# power_block.net
KiCad netlist of a schematic drawn in Altium Designer
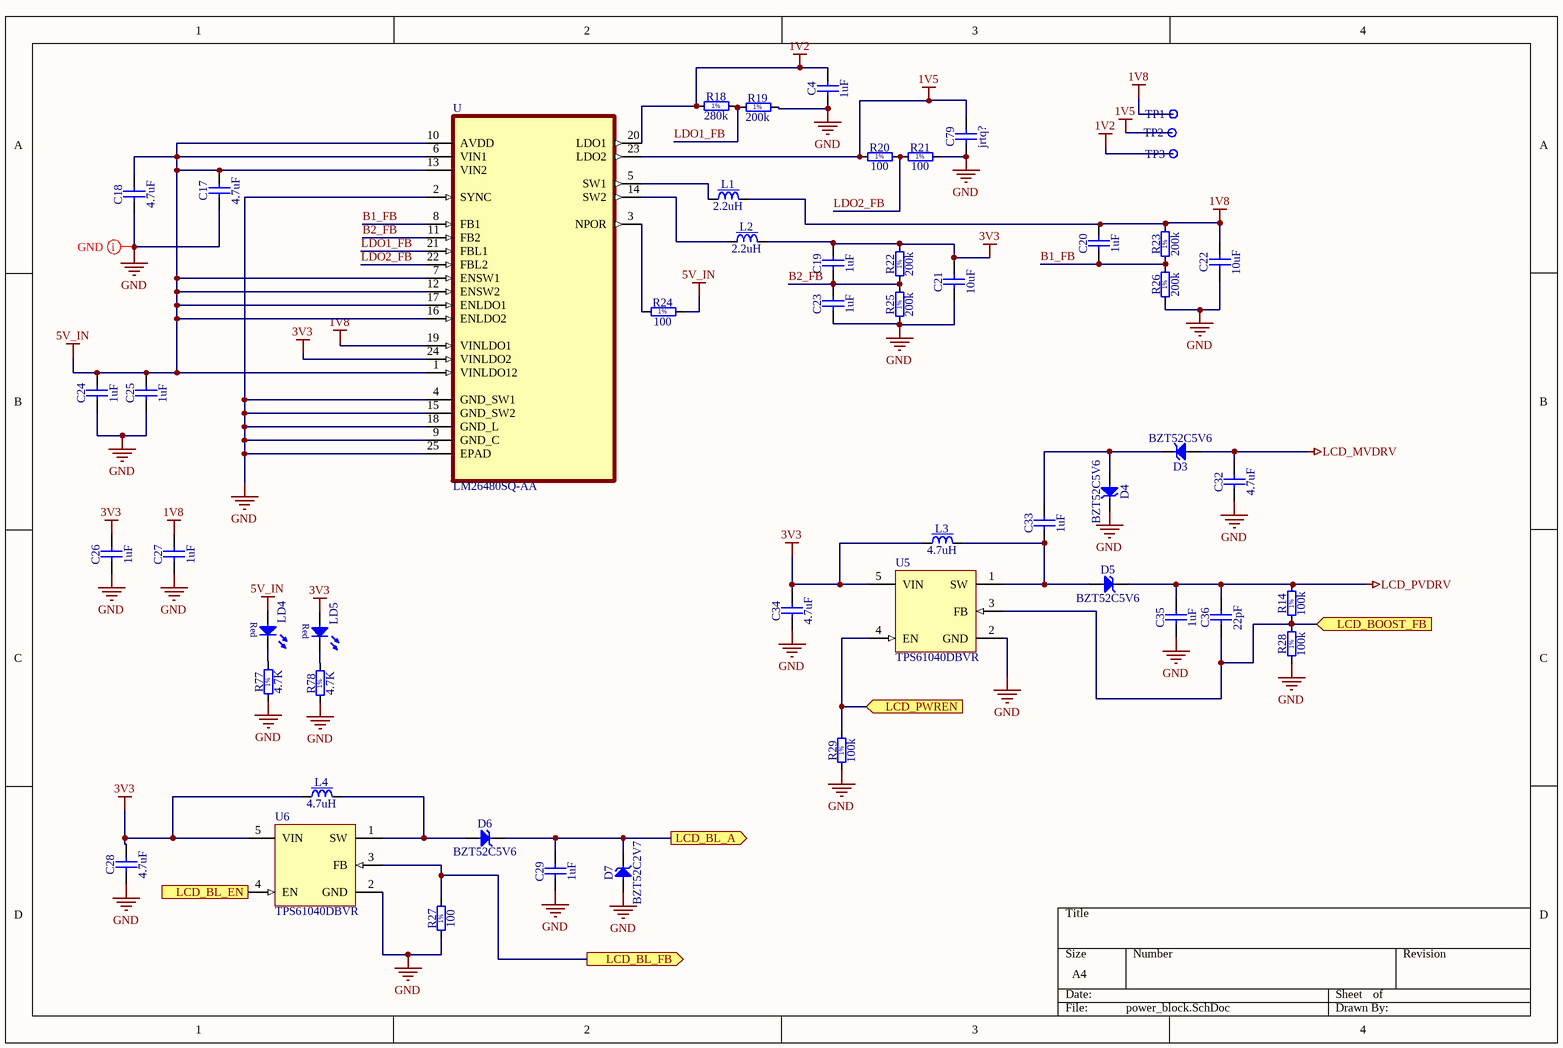
[diagram p0: power_block.SchDoc]

(export (version "E")
  (design (tool "Eeschema 10.0.6"))
  (components
    (comp (ref "C4")
      (value "1uF")
      (footprint "CAPC2013X100N")
      (description "Non-polarised capacitor")
      (fields
        (field (name "PART NUMBER") "CC0805_1.5NF_50V_5%_C0G")
        (field (name "VOLTAGE") "50V")
        (field (name "AUTHOR") "CERN DEM BC")
      )
      (libsource (lib "Capacitors") (part "Capacitor - non polarized"))
    )
    (comp (ref "C17")
      (value "4.7uF")
      (footprint "CAPC2013X100N")
      (description "Non-polarised capacitor")
      (fields
        (field (name "PART NUMBER") "CC0805_1.5NF_50V_5%_C0G")
        (field (name "VOLTAGE") "50V")
        (field (name "AUTHOR") "CERN DEM BC")
      )
      (libsource (lib "Capacitors") (part "Capacitor - non polarized"))
    )
    (comp (ref "C18")
      (value "4.7uF")
      (footprint "CAPC2013X100N")
      (description "Non-polarised capacitor")
      (fields
        (field (name "PART NUMBER") "CC0805_1.5NF_50V_5%_C0G")
        (field (name "VOLTAGE") "50V")
        (field (name "AUTHOR") "CERN DEM BC")
      )
      (libsource (lib "Capacitors") (part "Capacitor - non polarized"))
    )
    (comp (ref "C19")
      (value "1uF")
      (footprint "CAPC2013X100N")
      (description "Non-polarised capacitor")
      (fields
        (field (name "PART NUMBER") "CC0805_1.5NF_50V_5%_C0G")
        (field (name "VOLTAGE") "50V")
        (field (name "AUTHOR") "CERN DEM BC")
      )
      (libsource (lib "Capacitors") (part "Capacitor - non polarized"))
    )
    (comp (ref "C20")
      (value "1uF")
      (footprint "CAPC2013X100N")
      (description "Non-polarised capacitor")
      (fields
        (field (name "PART NUMBER") "CC0805_1.5NF_50V_5%_C0G")
        (field (name "VOLTAGE") "50V")
        (field (name "AUTHOR") "CERN DEM BC")
      )
      (libsource (lib "Capacitors") (part "Capacitor - non polarized"))
    )
    (comp (ref "C21")
      (value "10uF")
      (footprint "CAPC2013X100N")
      (description "Non-polarised capacitor")
      (fields
        (field (name "PART NUMBER") "CC0805_1.5NF_50V_5%_C0G")
        (field (name "VOLTAGE") "50V")
        (field (name "AUTHOR") "CERN DEM BC")
      )
      (libsource (lib "Capacitors") (part "Capacitor - non polarized"))
    )
    (comp (ref "C22")
      (value "10uF")
      (footprint "CAPC2013X100N")
      (description "Non-polarised capacitor")
      (fields
        (field (name "PART NUMBER") "CC0805_1.5NF_50V_5%_C0G")
        (field (name "VOLTAGE") "50V")
        (field (name "AUTHOR") "CERN DEM BC")
      )
      (libsource (lib "Capacitors") (part "Capacitor - non polarized"))
    )
    (comp (ref "C23")
      (value "1uF")
      (footprint "CAPC2013X100N")
      (description "Non-polarised capacitor")
      (fields
        (field (name "PART NUMBER") "CC0805_1.5NF_50V_5%_C0G")
        (field (name "VOLTAGE") "50V")
        (field (name "AUTHOR") "CERN DEM BC")
      )
      (libsource (lib "Capacitors") (part "Capacitor - non polarized"))
    )
    (comp (ref "C24")
      (value "1uF")
      (footprint "CAPC2013X100N")
      (description "Non-polarised capacitor")
      (fields
        (field (name "PART NUMBER") "CC0805_1.5NF_50V_5%_C0G")
        (field (name "VOLTAGE") "50V")
        (field (name "AUTHOR") "CERN DEM BC")
      )
      (libsource (lib "Capacitors") (part "Capacitor - non polarized"))
    )
    (comp (ref "C25")
      (value "1uF")
      (footprint "CAPC2013X100N")
      (description "Non-polarised capacitor")
      (fields
        (field (name "PART NUMBER") "CC0805_1.5NF_50V_5%_C0G")
        (field (name "VOLTAGE") "50V")
        (field (name "AUTHOR") "CERN DEM BC")
      )
      (libsource (lib "Capacitors") (part "Capacitor - non polarized"))
    )
    (comp (ref "C26")
      (value "1uF")
      (footprint "CAPC2013X100N")
      (description "Non-polarised capacitor")
      (fields
        (field (name "PART NUMBER") "CC0805_1.5NF_50V_5%_C0G")
        (field (name "VOLTAGE") "50V")
        (field (name "AUTHOR") "CERN DEM BC")
      )
      (libsource (lib "Capacitors") (part "Capacitor - non polarized"))
    )
    (comp (ref "C27")
      (value "1uF")
      (footprint "CAPC2013X100N")
      (description "Non-polarised capacitor")
      (fields
        (field (name "PART NUMBER") "CC0805_1.5NF_50V_5%_C0G")
        (field (name "VOLTAGE") "50V")
        (field (name "AUTHOR") "CERN DEM BC")
      )
      (libsource (lib "Capacitors") (part "Capacitor - non polarized"))
    )
    (comp (ref "C28")
      (value "4.7uF")
      (footprint "CAPC2013X100N")
      (description "Non-polarised capacitor")
      (fields
        (field (name "PART NUMBER") "CC0805_1.5NF_50V_5%_C0G")
        (field (name "VOLTAGE") "50V")
        (field (name "AUTHOR") "CERN DEM BC")
      )
      (libsource (lib "Capacitors") (part "Capacitor - non polarized"))
    )
    (comp (ref "C29")
      (value "1uF")
      (footprint "CAPC2013X100N")
      (description "Non-polarised capacitor")
      (fields
        (field (name "PART NUMBER") "CC0805_1.5NF_50V_5%_C0G")
        (field (name "VOLTAGE") "50V")
        (field (name "AUTHOR") "CERN DEM BC")
      )
      (libsource (lib "Capacitors") (part "Capacitor - non polarized"))
    )
    (comp (ref "C32")
      (value "4.7uF")
      (footprint "CAPC2013X100N")
      (description "Non-polarised capacitor")
      (fields
        (field (name "PART NUMBER") "CC0805_1.5NF_50V_5%_C0G")
        (field (name "VOLTAGE") "50V")
        (field (name "AUTHOR") "CERN DEM BC")
      )
      (libsource (lib "Capacitors") (part "Capacitor - non polarized"))
    )
    (comp (ref "C33")
      (value "1uF")
      (footprint "CAPC2013X100N")
      (description "Non-polarised capacitor")
      (fields
        (field (name "PART NUMBER") "CC0805_1.5NF_50V_5%_C0G")
        (field (name "VOLTAGE") "50V")
        (field (name "AUTHOR") "CERN DEM BC")
      )
      (libsource (lib "Capacitors") (part "Capacitor - non polarized"))
    )
    (comp (ref "C34")
      (value "4.7uF")
      (footprint "CAPC2013X100N")
      (description "Non-polarised capacitor")
      (fields
        (field (name "PART NUMBER") "CC0805_1.5NF_50V_5%_C0G")
        (field (name "VOLTAGE") "50V")
        (field (name "AUTHOR") "CERN DEM BC")
      )
      (libsource (lib "Capacitors") (part "Capacitor - non polarized"))
    )
    (comp (ref "C35")
      (value "1uF")
      (footprint "CAPC2013X100N")
      (description "Non-polarised capacitor")
      (fields
        (field (name "PART NUMBER") "CC0805_1.5NF_50V_5%_C0G")
        (field (name "VOLTAGE") "50V")
        (field (name "AUTHOR") "CERN DEM BC")
      )
      (libsource (lib "Capacitors") (part "Capacitor - non polarized"))
    )
    (comp (ref "C36")
      (value "22pF")
      (footprint "CAPC2013X100N")
      (description "Non-polarised capacitor")
      (fields
        (field (name "PART NUMBER") "CC0805_1.5NF_50V_5%_C0G")
        (field (name "VOLTAGE") "50V")
        (field (name "AUTHOR") "CERN DEM BC")
      )
      (libsource (lib "Capacitors") (part "Capacitor - non polarized"))
    )
    (comp (ref "C79")
      (value "jrtq?")
      (footprint "CAPC2013X100N")
      (description "Non-polarised capacitor")
      (fields
        (field (name "PART NUMBER") "CC0805_1.5NF_50V_5%_C0G")
        (field (name "VOLTAGE") "50V")
        (field (name "AUTHOR") "CERN DEM BC")
      )
      (libsource (lib "Capacitors") (part "Capacitor - non polarized"))
    )
    (comp (ref "D3")
      (value "BZT52C5V6")
      (footprint "SOD3715X145N")
      (description "Zener Diode")
      (fields
        (field (name "VOLTAGE") "5V6")
        (field (name "POWER") "0.5W")
        (field (name "AUTHOR") "CERN DEM JLC")
      )
      (libsource (lib "ICs And Semiconductors") (part "Diode Zener"))
    )
    (comp (ref "D4")
      (value "BZT52C5V6")
      (footprint "SOD3715X145N")
      (description "Zener Diode")
      (fields
        (field (name "VOLTAGE") "5V6")
        (field (name "POWER") "0.5W")
        (field (name "AUTHOR") "CERN DEM JLC")
      )
      (libsource (lib "ICs And Semiconductors") (part "Diode Zener"))
    )
    (comp (ref "D5")
      (value "BZT52C5V6")
      (footprint "SOD3715X145N")
      (description "Zener Diode")
      (fields
        (field (name "VOLTAGE") "5V6")
        (field (name "POWER") "0.5W")
        (field (name "AUTHOR") "CERN DEM JLC")
      )
      (libsource (lib "ICs And Semiconductors") (part "Diode Zener"))
    )
    (comp (ref "D6")
      (value "BZT52C5V6")
      (footprint "SOD3715X145N")
      (description "Zener Diode")
      (fields
        (field (name "VOLTAGE") "5V6")
        (field (name "POWER") "0.5W")
        (field (name "AUTHOR") "CERN DEM JLC")
      )
      (libsource (lib "ICs And Semiconductors") (part "Diode Zener"))
    )
    (comp (ref "D7")
      (value "BZT52C2V7")
      (footprint "SOD3715X145N")
      (description "Zener Diode")
      (fields
        (field (name "VOLTAGE") "2V7")
        (field (name "POWER") "500mW")
        (field (name "AUTHOR") "CERN DEM JLC")
      )
      (libsource (lib "ICs And Semiconductors") (part "Diode Zener"))
    )
    (comp (ref "L1")
      (value "2.2uH")
      (footprint "IND_MURATA-PS_8200")
      (description "Inductor With Core")
      (fields
        (field (name "PART NUMBER") "IND_22UH_10%_MURATA-PS_8200")
        (field (name "POWER") "320mA")
        (field (name "AUTHOR") "CERN DEM JMW")
      )
      (libsource (lib "Inductors & Transformers") (part "Inductor With Magnetic core"))
    )
    (comp (ref "L2")
      (value "2.2uH")
      (footprint "IND_MURATA-PS_8200")
      (description "Inductor With Core")
      (fields
        (field (name "PART NUMBER") "IND_22UH_10%_MURATA-PS_8200")
        (field (name "POWER") "320mA")
        (field (name "AUTHOR") "CERN DEM JMW")
      )
      (libsource (lib "Inductors & Transformers") (part "Inductor With Magnetic core"))
    )
    (comp (ref "L3")
      (value "4.7uH")
      (footprint "IND_MURATA-PS_8200")
      (description "Inductor With Core")
      (fields
        (field (name "PART NUMBER") "IND_22UH_10%_MURATA-PS_8200")
        (field (name "POWER") "320mA")
        (field (name "AUTHOR") "CERN DEM JMW")
      )
      (libsource (lib "Inductors & Transformers") (part "Inductor With Magnetic core"))
    )
    (comp (ref "L4")
      (value "4.7uH")
      (footprint "IND_MURATA-PS_8200")
      (description "Inductor With Core")
      (fields
        (field (name "PART NUMBER") "IND_22UH_10%_MURATA-PS_8200")
        (field (name "POWER") "320mA")
        (field (name "AUTHOR") "CERN DEM JMW")
      )
      (libsource (lib "Inductors & Transformers") (part "Inductor With Magnetic core"))
    )
    (comp (ref "LD4")
      (value "Super Red")
      (footprint "LED_OSRAM_LSR976")
      (description "LED Red 1C 2A")
      (fields
        (field (name "PART NUMBER") "LED_OSRAM_LSR976")
        (field (name "MANUFACTURER") "OSRAM")
        (field (name "AUTHOR") "CERN DEM JLC")
      )
      (libsource (lib "ICs And Semiconductors") (part "LED Red 1C 2A"))
    )
    (comp (ref "LD5")
      (value "Super Red")
      (footprint "LED_OSRAM_LSR976")
      (description "LED Red 1C 2A")
      (fields
        (field (name "PART NUMBER") "LED_OSRAM_LSR976")
        (field (name "MANUFACTURER") "OSRAM")
        (field (name "AUTHOR") "CERN DEM JLC")
      )
      (libsource (lib "ICs And Semiconductors") (part "LED Red 1C 2A"))
    )
    (comp (ref "R14")
      (value "100k")
      (footprint "RESC1608X55N")
      (description "Resistor - 1%")
      (fields
        (field (name "PART NUMBER") "R0603_100K_1%_0.1W_100PPM")
        (field (name "POWER") "0.1W")
        (field (name "AUTHOR") "CERN DEM JLC")
      )
      (libsource (lib "Resistors") (part "Resistor - 1%"))
    )
    (comp (ref "R18")
      (value "280k")
      (footprint "RESC1608X55N")
      (description "Resistor - 1%")
      (fields
        (field (name "PART NUMBER") "R0603_100K_1%_0.1W_100PPM")
        (field (name "POWER") "0.1W")
        (field (name "AUTHOR") "CERN DEM JLC")
      )
      (libsource (lib "Resistors") (part "Resistor - 1%"))
    )
    (comp (ref "R19")
      (value "200k")
      (footprint "RESC1608X55N")
      (description "Resistor - 1%")
      (fields
        (field (name "PART NUMBER") "R0603_100K_1%_0.1W_100PPM")
        (field (name "POWER") "0.1W")
        (field (name "AUTHOR") "CERN DEM JLC")
      )
      (libsource (lib "Resistors") (part "Resistor - 1%"))
    )
    (comp (ref "R20")
      (value "100")
      (footprint "RESC1608X55N")
      (description "Resistor - 1%")
      (fields
        (field (name "PART NUMBER") "R0603_100K_1%_0.1W_100PPM")
        (field (name "POWER") "0.1W")
        (field (name "AUTHOR") "CERN DEM JLC")
      )
      (libsource (lib "Resistors") (part "Resistor - 1%"))
    )
    (comp (ref "R21")
      (value "100")
      (footprint "RESC1608X55N")
      (description "Resistor - 1%")
      (fields
        (field (name "PART NUMBER") "R0603_100K_1%_0.1W_100PPM")
        (field (name "POWER") "0.1W")
        (field (name "AUTHOR") "CERN DEM JLC")
      )
      (libsource (lib "Resistors") (part "Resistor - 1%"))
    )
    (comp (ref "R22")
      (value "200k")
      (footprint "RESC1608X55N")
      (description "Resistor - 1%")
      (fields
        (field (name "PART NUMBER") "R0603_100K_1%_0.1W_100PPM")
        (field (name "POWER") "0.1W")
        (field (name "AUTHOR") "CERN DEM JLC")
      )
      (libsource (lib "Resistors") (part "Resistor - 1%"))
    )
    (comp (ref "R23")
      (value "200k")
      (footprint "RESC1608X55N")
      (description "Resistor - 1%")
      (fields
        (field (name "PART NUMBER") "R0603_100K_1%_0.1W_100PPM")
        (field (name "POWER") "0.1W")
        (field (name "AUTHOR") "CERN DEM JLC")
      )
      (libsource (lib "Resistors") (part "Resistor - 1%"))
    )
    (comp (ref "R24")
      (value "100")
      (footprint "RESC1608X55N")
      (description "Resistor - 1%")
      (fields
        (field (name "PART NUMBER") "R0603_100K_1%_0.1W_100PPM")
        (field (name "POWER") "0.1W")
        (field (name "AUTHOR") "CERN DEM JLC")
      )
      (libsource (lib "Resistors") (part "Resistor - 1%"))
    )
    (comp (ref "R25")
      (value "200k")
      (footprint "RESC1608X55N")
      (description "Resistor - 1%")
      (fields
        (field (name "PART NUMBER") "R0603_100K_1%_0.1W_100PPM")
        (field (name "POWER") "0.1W")
        (field (name "AUTHOR") "CERN DEM JLC")
      )
      (libsource (lib "Resistors") (part "Resistor - 1%"))
    )
    (comp (ref "R26")
      (value "200k")
      (footprint "RESC1608X55N")
      (description "Resistor - 1%")
      (fields
        (field (name "PART NUMBER") "R0603_100K_1%_0.1W_100PPM")
        (field (name "POWER") "0.1W")
        (field (name "AUTHOR") "CERN DEM JLC")
      )
      (libsource (lib "Resistors") (part "Resistor - 1%"))
    )
    (comp (ref "R27")
      (value "100")
      (footprint "RESC1608X55N")
      (description "Resistor - 1%")
      (fields
        (field (name "PART NUMBER") "R0603_100K_1%_0.1W_100PPM")
        (field (name "POWER") "0.1W")
        (field (name "AUTHOR") "CERN DEM JLC")
      )
      (libsource (lib "Resistors") (part "Resistor - 1%"))
    )
    (comp (ref "R28")
      (value "100k")
      (footprint "RESC1608X55N")
      (description "Resistor - 1%")
      (fields
        (field (name "PART NUMBER") "R0603_100K_1%_0.1W_100PPM")
        (field (name "POWER") "0.1W")
        (field (name "AUTHOR") "CERN DEM JLC")
      )
      (libsource (lib "Resistors") (part "Resistor - 1%"))
    )
    (comp (ref "R29")
      (value "100k")
      (footprint "RESC1608X55N")
      (description "Resistor - 1%")
      (fields
        (field (name "PART NUMBER") "R0603_100K_1%_0.1W_100PPM")
        (field (name "POWER") "0.1W")
        (field (name "AUTHOR") "CERN DEM JLC")
      )
      (libsource (lib "Resistors") (part "Resistor - 1%"))
    )
    (comp (ref "R77")
      (value "4.7K")
      (footprint "RESC1608X55N")
      (description "Resistor - 1%")
      (fields
        (field (name "PART NUMBER") "R0603_100K_1%_0.1W_100PPM")
        (field (name "POWER") "0.1W")
        (field (name "AUTHOR") "CERN DEM JLC")
      )
      (libsource (lib "Resistors") (part "Resistor - 1%"))
    )
    (comp (ref "R78")
      (value "4.7K")
      (footprint "RESC1608X55N")
      (description "Resistor - 1%")
      (fields
        (field (name "PART NUMBER") "R0603_100K_1%_0.1W_100PPM")
        (field (name "POWER") "0.1W")
        (field (name "AUTHOR") "CERN DEM JLC")
      )
      (libsource (lib "Resistors") (part "Resistor - 1%"))
    )
    (comp (ref "TP1")
      (value "Test Point")
      (footprint "TPS127")
      (fields (field (name "PART NUMBER") "SMD_PAD_1.27X1.27MM") (field (name "AUTHOR") "CERN DEM JLC"))
      (libsource (lib "Eletro-mechanical") (part "Test Point"))
    )
    (comp (ref "TP2")
      (value "Test Point")
      (footprint "TPS127")
      (fields (field (name "PART NUMBER") "SMD_PAD_1.27X1.27MM") (field (name "AUTHOR") "CERN DEM JLC"))
      (libsource (lib "Eletro-mechanical") (part "Test Point"))
    )
    (comp (ref "TP3")
      (value "Test Point")
      (footprint "TPS127")
      (fields (field (name "PART NUMBER") "SMD_PAD_1.27X1.27MM") (field (name "AUTHOR") "CERN DEM JLC"))
      (libsource (lib "Eletro-mechanical") (part "Test Point"))
    )
    (comp (ref "U")
      (value "LM26480SQ-AA")
      (footprint "QFN400X400X80-25N")
      (fields (field (name "MF") "Texas Instruments"))
      (libsource (lib "LM26480SQ-AA") (part "LM26480SQ-AA"))
    )
    (comp (ref "U5")
      (value "TPS61040DBVR")
      (footprint "TI-DBV5_L")
      (fields (field (name "MANUFACTURER") "Texas Instruments"))
      (libsource (lib "TI Power Management Lighting and Display") (part "TPS61040DBVR"))
    )
    (comp (ref "U6")
      (value "TPS61040DBVR")
      (footprint "TI-DBV5_L")
      (fields (field (name "MANUFACTURER") "Texas Instruments"))
      (libsource (lib "TI Power Management Lighting and Display") (part "TPS61040DBVR"))
    )
  )
  (nets
    (net (code "1") (name "/B1_FB") (class "Default")
      (node (ref "C20") (pin "1") (pinfunction "1_1") (pintype "passive"))
      (node (ref "R23") (pin "1") (pinfunction "1_1") (pintype "passive"))
      (node (ref "R26") (pin "2") (pinfunction "2_2") (pintype "passive"))
      (node (ref "U") (pin "8") (pinfunction "FB1_8") (pintype "input"))
    )
    (net (code "2") (name "/B2_FB") (class "Default")
      (node (ref "C19") (pin "1") (pinfunction "1_1") (pintype "passive"))
      (node (ref "C23") (pin "2") (pinfunction "2_2") (pintype "passive"))
      (node (ref "R22") (pin "1") (pinfunction "1_1") (pintype "passive"))
      (node (ref "R25") (pin "2") (pinfunction "2_2") (pintype "passive"))
      (node (ref "U") (pin "11") (pinfunction "FB2_11") (pintype "input"))
    )
    (net (code "3") (name "/LCD_BL_A") (class "Default")
      (node (ref "C29") (pin "2") (pinfunction "2_2") (pintype "passive"))
      (node (ref "D6") (pin "1") (pinfunction "C_1") (pintype "passive"))
      (node (ref "D7") (pin "1") (pinfunction "C_1") (pintype "passive"))
    )
    (net (code "4") (name "/LCD_BL_EN") (class "Default")
      (node (ref "U6") (pin "4") (pinfunction "EN_4") (pintype "input"))
    )
    (net (code "5") (name "/LCD_BL_FB") (class "Default")
      (node (ref "R27") (pin "2") (pinfunction "2_2") (pintype "passive"))
      (node (ref "U6") (pin "3") (pinfunction "FB_3") (pintype "input"))
    )
    (net (code "6") (name "/LCD_BOOST_FB") (class "Default")
      (node (ref "C36") (pin "1") (pinfunction "1_1") (pintype "passive"))
      (node (ref "R14") (pin "1") (pinfunction "1_1") (pintype "passive"))
      (node (ref "R28") (pin "2") (pinfunction "2_2") (pintype "passive"))
      (node (ref "U5") (pin "3") (pinfunction "FB_3") (pintype "input"))
    )
    (net (code "7") (name "/LCD_PWREN") (class "Default")
      (node (ref "R29") (pin "2") (pinfunction "2_2") (pintype "passive"))
      (node (ref "U5") (pin "4") (pinfunction "EN_4") (pintype "input"))
    )
    (net (code "8") (name "/LDO1_FB") (class "Default")
      (node (ref "R18") (pin "2") (pinfunction "2_2") (pintype "passive"))
      (node (ref "R19") (pin "1") (pinfunction "1_1") (pintype "passive"))
      (node (ref "U") (pin "21") (pinfunction "FBL1_21") (pintype "input"))
    )
    (net (code "9") (name "/LDO2_FB") (class "Default")
      (node (ref "R20") (pin "2") (pinfunction "2_2") (pintype "passive"))
      (node (ref "R21") (pin "1") (pinfunction "1_1") (pintype "passive"))
      (node (ref "U") (pin "22") (pinfunction "FBL2_22") (pintype "input"))
    )
    (net (code "10") (name "1V2") (class "Default")
      (node (ref "C4") (pin "2") (pinfunction "2_2") (pintype "passive"))
      (node (ref "R18") (pin "1") (pinfunction "1_1") (pintype "passive"))
      (node (ref "TP3") (pin "1") (pinfunction "1_1") (pintype "bidirectional"))
      (node (ref "U") (pin "20") (pinfunction "LDO1_20") (pintype "output"))
    )
    (net (code "11") (name "1V5") (class "Default")
      (node (ref "C79") (pin "2") (pinfunction "2_2") (pintype "passive"))
      (node (ref "R20") (pin "1") (pinfunction "1_1") (pintype "passive"))
      (node (ref "TP2") (pin "1") (pinfunction "1_1") (pintype "bidirectional"))
      (node (ref "U") (pin "23") (pinfunction "LDO2_23") (pintype "output"))
    )
    (net (code "12") (name "1V8") (class "Default")
      (node (ref "C20") (pin "2") (pinfunction "2_2") (pintype "passive"))
      (node (ref "C22") (pin "2") (pinfunction "2_2") (pintype "passive"))
      (node (ref "C27") (pin "2") (pinfunction "2_2") (pintype "passive"))
      (node (ref "L1") (pin "2") (pinfunction "2_2") (pintype "passive"))
      (node (ref "R23") (pin "2") (pinfunction "2_2") (pintype "passive"))
      (node (ref "TP1") (pin "1") (pinfunction "1_1") (pintype "bidirectional"))
      (node (ref "U") (pin "19") (pinfunction "VINLDO1_19") (pintype "input"))
    )
    (net (code "13") (name "3V3") (class "Default")
      (node (ref "C19") (pin "2") (pinfunction "2_2") (pintype "passive"))
      (node (ref "C21") (pin "2") (pinfunction "2_2") (pintype "passive"))
      (node (ref "C26") (pin "2") (pinfunction "2_2") (pintype "passive"))
      (node (ref "C28") (pin "2") (pinfunction "2_2") (pintype "passive"))
      (node (ref "C34") (pin "2") (pinfunction "2_2") (pintype "passive"))
      (node (ref "L2") (pin "2") (pinfunction "2_2") (pintype "passive"))
      (node (ref "L3") (pin "1") (pinfunction "1_1") (pintype "passive"))
      (node (ref "L4") (pin "1") (pinfunction "1_1") (pintype "passive"))
      (node (ref "LD5") (pin "2") (pinfunction "A_2") (pintype "passive"))
      (node (ref "R22") (pin "2") (pinfunction "2_2") (pintype "passive"))
      (node (ref "U") (pin "24") (pinfunction "VINLDO2_24") (pintype "input"))
      (node (ref "U5") (pin "5") (pinfunction "VIN_5") (pintype "power_in"))
      (node (ref "U6") (pin "5") (pinfunction "VIN_5") (pintype "power_in"))
    )
    (net (code "14") (name "5V_IN") (class "Default")
      (node (ref "C17") (pin "2") (pinfunction "2_2") (pintype "passive"))
      (node (ref "C18") (pin "2") (pinfunction "2_2") (pintype "passive"))
      (node (ref "C24") (pin "2") (pinfunction "2_2") (pintype "passive"))
      (node (ref "C25") (pin "2") (pinfunction "2_2") (pintype "passive"))
      (node (ref "LD4") (pin "2") (pinfunction "A_2") (pintype "passive"))
      (node (ref "R24") (pin "2") (pinfunction "2_2") (pintype "passive"))
      (node (ref "U") (pin "1") (pinfunction "VINLDO12_1") (pintype "input"))
      (node (ref "U") (pin "10") (pinfunction "AVDD_10") (pintype "power_in"))
      (node (ref "U") (pin "12") (pinfunction "ENSW2_12") (pintype "input"))
      (node (ref "U") (pin "13") (pinfunction "VIN2_13") (pintype "power_in"))
      (node (ref "U") (pin "16") (pinfunction "ENLDO2_16") (pintype "input"))
      (node (ref "U") (pin "17") (pinfunction "ENLDO1_17") (pintype "input"))
      (node (ref "U") (pin "6") (pinfunction "VIN1_6") (pintype "power_in"))
      (node (ref "U") (pin "7") (pinfunction "ENSW1_7") (pintype "input"))
    )
    (net (code "15") (name "GND") (class "Default")
      (node (ref "C17") (pin "1") (pinfunction "1_1") (pintype "passive"))
      (node (ref "C18") (pin "1") (pinfunction "1_1") (pintype "passive"))
      (node (ref "C21") (pin "1") (pinfunction "1_1") (pintype "passive"))
      (node (ref "C22") (pin "1") (pinfunction "1_1") (pintype "passive"))
      (node (ref "C23") (pin "1") (pinfunction "1_1") (pintype "passive"))
      (node (ref "C24") (pin "1") (pinfunction "1_1") (pintype "passive"))
      (node (ref "C25") (pin "1") (pinfunction "1_1") (pintype "passive"))
      (node (ref "C26") (pin "1") (pinfunction "1_1") (pintype "passive"))
      (node (ref "C27") (pin "1") (pinfunction "1_1") (pintype "passive"))
      (node (ref "C28") (pin "1") (pinfunction "1_1") (pintype "passive"))
      (node (ref "C29") (pin "1") (pinfunction "1_1") (pintype "passive"))
      (node (ref "C32") (pin "1") (pinfunction "1_1") (pintype "passive"))
      (node (ref "C34") (pin "1") (pinfunction "1_1") (pintype "passive"))
      (node (ref "C35") (pin "1") (pinfunction "1_1") (pintype "passive"))
      (node (ref "C4") (pin "1") (pinfunction "1_1") (pintype "passive"))
      (node (ref "C79") (pin "1") (pinfunction "1_1") (pintype "passive"))
      (node (ref "D4") (pin "1") (pinfunction "C_1") (pintype "passive"))
      (node (ref "D7") (pin "2") (pinfunction "A_2") (pintype "passive"))
      (node (ref "R19") (pin "2") (pinfunction "2_2") (pintype "passive"))
      (node (ref "R21") (pin "2") (pinfunction "2_2") (pintype "passive"))
      (node (ref "R25") (pin "1") (pinfunction "1_1") (pintype "passive"))
      (node (ref "R26") (pin "1") (pinfunction "1_1") (pintype "passive"))
      (node (ref "R27") (pin "1") (pinfunction "1_1") (pintype "passive"))
      (node (ref "R28") (pin "1") (pinfunction "1_1") (pintype "passive"))
      (node (ref "R29") (pin "1") (pinfunction "1_1") (pintype "passive"))
      (node (ref "R77") (pin "1") (pinfunction "1_1") (pintype "passive"))
      (node (ref "R78") (pin "1") (pinfunction "1_1") (pintype "passive"))
      (node (ref "U") (pin "15") (pinfunction "GND_SW2_15") (pintype "passive"))
      (node (ref "U") (pin "18") (pinfunction "GND_L_18") (pintype "passive"))
      (node (ref "U") (pin "2") (pinfunction "SYNC_2") (pintype "input"))
      (node (ref "U") (pin "25") (pinfunction "EPAD_25") (pintype "passive"))
      (node (ref "U") (pin "4") (pinfunction "GND_SW1_4") (pintype "passive"))
      (node (ref "U") (pin "9") (pinfunction "GND_C_9") (pintype "passive"))
      (node (ref "U5") (pin "2") (pinfunction "GND_2") (pintype "power_in"))
      (node (ref "U6") (pin "2") (pinfunction "GND_2") (pintype "power_in"))
    )
    (net (code "16") (name "LCD_MVDRV") (class "Default")
      (node (ref "C32") (pin "2") (pinfunction "2_2") (pintype "passive"))
      (node (ref "D3") (pin "2") (pinfunction "A_2") (pintype "passive"))
    )
    (net (code "17") (name "LCD_PVDRV") (class "Default")
      (node (ref "C35") (pin "2") (pinfunction "2_2") (pintype "passive"))
      (node (ref "C36") (pin "2") (pinfunction "2_2") (pintype "passive"))
      (node (ref "D5") (pin "1") (pinfunction "C_1") (pintype "passive"))
      (node (ref "R14") (pin "2") (pinfunction "2_2") (pintype "passive"))
    )
    (net (code "18") (name "Net-(D3-C)") (class "Default")
      (node (ref "C33") (pin "2") (pinfunction "2_2") (pintype "passive"))
      (node (ref "D3") (pin "1") (pinfunction "C_1") (pintype "passive"))
      (node (ref "D4") (pin "2") (pinfunction "A_2") (pintype "passive"))
    )
    (net (code "19") (name "Net-(D5-A)") (class "Default")
      (node (ref "C33") (pin "1") (pinfunction "1_1") (pintype "passive"))
      (node (ref "D5") (pin "2") (pinfunction "A_2") (pintype "passive"))
      (node (ref "L3") (pin "2") (pinfunction "2_2") (pintype "passive"))
      (node (ref "U5") (pin "1") (pinfunction "SW_1") (pintype "power_in"))
    )
    (net (code "20") (name "Net-(D6-A)") (class "Default")
      (node (ref "D6") (pin "2") (pinfunction "A_2") (pintype "passive"))
      (node (ref "L4") (pin "2") (pinfunction "2_2") (pintype "passive"))
      (node (ref "U6") (pin "1") (pinfunction "SW_1") (pintype "power_in"))
    )
    (net (code "21") (name "Net-(LD4-C)") (class "Default")
      (node (ref "LD4") (pin "1") (pinfunction "C_1") (pintype "passive"))
      (node (ref "R77") (pin "2") (pinfunction "2_2") (pintype "passive"))
    )
    (net (code "22") (name "Net-(LD5-C)") (class "Default")
      (node (ref "LD5") (pin "1") (pinfunction "C_1") (pintype "passive"))
      (node (ref "R78") (pin "2") (pinfunction "2_2") (pintype "passive"))
    )
    (net (code "23") (name "Net-(U-NPOR)") (class "Default")
      (node (ref "R24") (pin "1") (pinfunction "1_1") (pintype "passive"))
      (node (ref "U") (pin "3") (pinfunction "NPOR_3") (pintype "output"))
    )
    (net (code "24") (name "Net-(U-SW1)") (class "Default")
      (node (ref "L1") (pin "1") (pinfunction "1_1") (pintype "passive"))
      (node (ref "U") (pin "5") (pinfunction "SW1_5") (pintype "output"))
    )
    (net (code "25") (name "Net-(U-SW2)") (class "Default")
      (node (ref "L2") (pin "1") (pinfunction "1_1") (pintype "passive"))
      (node (ref "U") (pin "14") (pinfunction "SW2_14") (pintype "output"))
    )
  )
)
